# hub_exterior.net
KiCad netlist of a schematic drawn in EAGLE
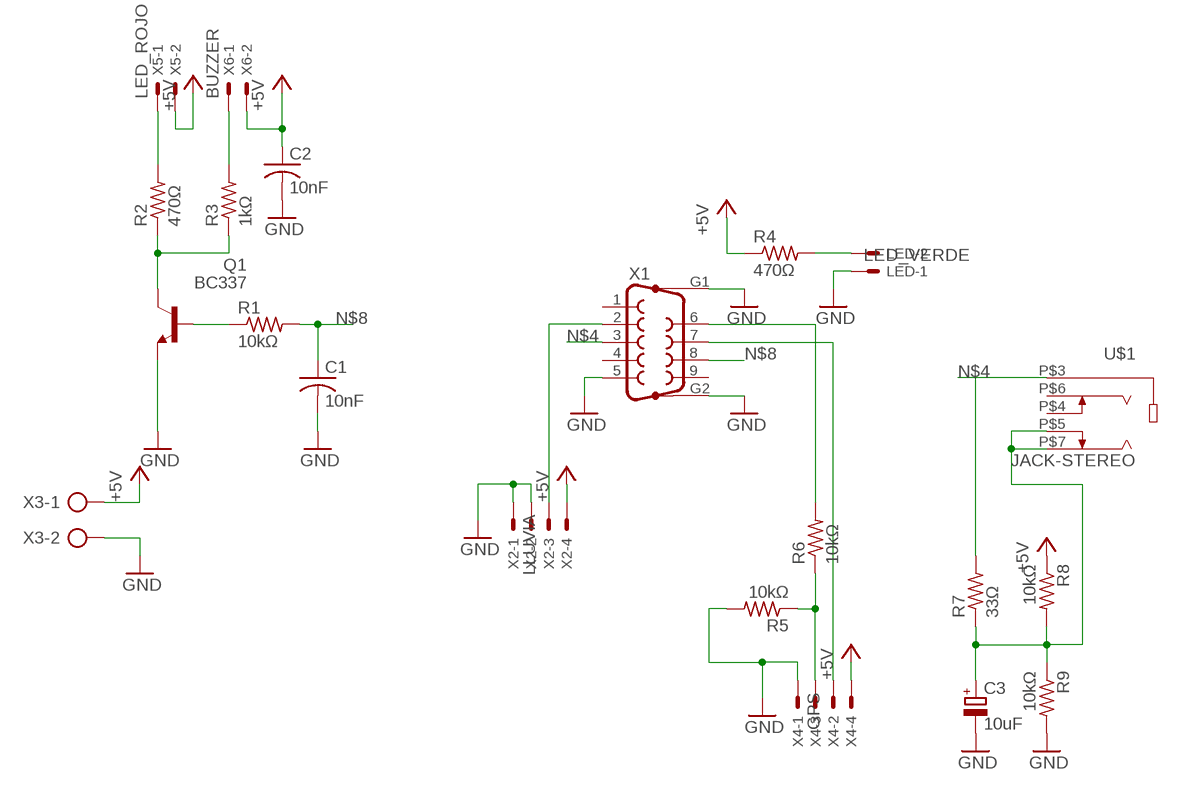
[diagram p0: schematic, sheet 1]

(export (version "E")
  (design (tool "Eeschema 10.0.6"))
  (components
    (comp (ref "C1")
      (value "10nF")
      (footprint "eagle-import:C050-025X075")
      (libsource (lib "eagle-import") (part "C-US050-025X075"))
    )
    (comp (ref "C2")
      (value "10nF")
      (footprint "eagle-import:C050-025X075")
      (libsource (lib "eagle-import") (part "C-US050-025X075"))
    )
    (comp (ref "C3")
      (value "10uF")
      (footprint "eagle-import:E2,5-5")
      (libsource (lib "eagle-import") (part "CPOL-EUE2.5-5"))
    )
    (comp (ref "LED")
      (value "LED_VERDE")
      (footprint "eagle-import:22-23-2021")
      (fields (field (name "MF") "MOLEX") (field (name "MPN") "22-23-2021"))
      (libsource (lib "eagle-import") (part "22-23-2021"))
    )
    (comp (ref "Q1")
      (value "BC337")
      (footprint "eagle-import:TO92")
      (libsource (lib "eagle-import") (part "BC337"))
    )
    (comp (ref "R1")
      (value "10kΩ")
      (footprint "eagle-import:0207_7")
      (libsource (lib "eagle-import") (part "R-US_0207/7"))
    )
    (comp (ref "R2")
      (value "470Ω")
      (footprint "eagle-import:0207_7")
      (libsource (lib "eagle-import") (part "R-US_0207/7"))
    )
    (comp (ref "R3")
      (value "1kΩ")
      (footprint "eagle-import:0207_7")
      (libsource (lib "eagle-import") (part "R-US_0207/7"))
    )
    (comp (ref "R4")
      (value "470Ω")
      (footprint "eagle-import:0207_7")
      (libsource (lib "eagle-import") (part "R-US_0207/7"))
    )
    (comp (ref "R5")
      (value "10kΩ")
      (footprint "eagle-import:0207_7")
      (libsource (lib "eagle-import") (part "R-US_0207/7"))
    )
    (comp (ref "R6")
      (value "10kΩ")
      (footprint "eagle-import:0207_15")
      (libsource (lib "eagle-import") (part "R-US_0207/15"))
    )
    (comp (ref "R7")
      (value "33Ω")
      (footprint "eagle-import:0207_7")
      (libsource (lib "eagle-import") (part "R-US_0207/7"))
    )
    (comp (ref "R8")
      (value "10kΩ")
      (footprint "eagle-import:0207_7")
      (libsource (lib "eagle-import") (part "R-US_0207/7"))
    )
    (comp (ref "R9")
      (value "10kΩ")
      (footprint "eagle-import:0207_7")
      (libsource (lib "eagle-import") (part "R-US_0207/7"))
    )
    (comp (ref "U$1")
      (value "JACK-STEREO")
      (footprint "eagle-import:SPC21348")
      (libsource (lib "eagle-import") (part "JACK-STEREO"))
    )
    (comp (ref "X1")
      (value "F09HP")
      (footprint "eagle-import:F09HP")
      (libsource (lib "eagle-import") (part "F09HP"))
    )
    (comp (ref "X2")
      (value "LLUVIA")
      (footprint "eagle-import:22-23-2041")
      (fields (field (name "MF") "MOLEX") (field (name "MPN") "22-23-2041"))
      (libsource (lib "eagle-import") (part "22-23-2041"))
    )
    (comp (ref "X3")
      (value "AK500/2")
      (footprint "eagle-import:AK500_2")
      (libsource (lib "eagle-import") (part "AK500/2"))
    )
    (comp (ref "X4")
      (value "GPS")
      (footprint "eagle-import:22-23-2041")
      (fields (field (name "MF") "MOLEX") (field (name "MPN") "22-23-2041"))
      (libsource (lib "eagle-import") (part "22-23-2041"))
    )
    (comp (ref "X5")
      (value "LED_ROJO")
      (footprint "eagle-import:22-23-2021")
      (fields (field (name "MF") "MOLEX") (field (name "MPN") "22-23-2021"))
      (libsource (lib "eagle-import") (part "22-23-2021"))
    )
    (comp (ref "X6")
      (value "BUZZER")
      (footprint "eagle-import:22-23-2021")
      (fields (field (name "MF") "MOLEX") (field (name "MPN") "22-23-2021"))
      (libsource (lib "eagle-import") (part "22-23-2021"))
    )
  )
  (nets
    (net (code "1") (name "+5V") (class "Default")
      (node (ref "C2") (pin "1") (pinfunction "1_1") (pintype "passive"))
      (node (ref "R4") (pin "1") (pinfunction "1_1") (pintype "passive"))
      (node (ref "R8") (pin "1") (pinfunction "1_1") (pintype "passive"))
      (node (ref "X2") (pin "4") (pinfunction "S_4") (pintype "passive"))
      (node (ref "X3") (pin "1") (pinfunction "KL_1") (pintype "passive"))
      (node (ref "X4") (pin "4") (pinfunction "S_4") (pintype "passive"))
      (node (ref "X5") (pin "2") (pinfunction "S_2") (pintype "passive"))
      (node (ref "X6") (pin "2") (pinfunction "S_2") (pintype "passive"))
    )
    (net (code "2") (name "/N$4") (class "Default")
      (node (ref "R7") (pin "2") (pinfunction "2_2") (pintype "passive"))
      (node (ref "U$1") (pin "P$3") (pinfunction "1_P$3") (pintype "passive"))
      (node (ref "X1") (pin "3") (pinfunction "3_3") (pintype "passive"))
    )
    (net (code "3") (name "/N$8") (class "Default")
      (node (ref "C1") (pin "1") (pinfunction "1_1") (pintype "passive"))
      (node (ref "R1") (pin "2") (pinfunction "2_2") (pintype "passive"))
      (node (ref "X1") (pin "8") (pinfunction "8_8") (pintype "passive"))
    )
    (net (code "4") (name "GND") (class "Default")
      (node (ref "C1") (pin "2") (pinfunction "2_2") (pintype "passive"))
      (node (ref "C2") (pin "2") (pinfunction "2_2") (pintype "passive"))
      (node (ref "C3") (pin "-") (pinfunction "-_-") (pintype "passive"))
      (node (ref "LED") (pin "1") (pinfunction "S_1") (pintype "passive"))
      (node (ref "Q1") (pin "1") (pinfunction "E_1") (pintype "passive"))
      (node (ref "R5") (pin "2") (pinfunction "2_2") (pintype "passive"))
      (node (ref "R9") (pin "2") (pinfunction "2_2") (pintype "passive"))
      (node (ref "X1") (pin "5") (pinfunction "5_5") (pintype "passive"))
      (node (ref "X1") (pin "G1") (pinfunction "G1_G1") (pintype "passive"))
      (node (ref "X1") (pin "G2") (pinfunction "G2_G2") (pintype "passive"))
      (node (ref "X2") (pin "1") (pinfunction "S_1") (pintype "passive"))
      (node (ref "X2") (pin "2") (pinfunction "S_2") (pintype "passive"))
      (node (ref "X3") (pin "2") (pinfunction "KL_2") (pintype "passive"))
      (node (ref "X4") (pin "1") (pinfunction "S_1") (pintype "passive"))
    )
    (net (code "5") (name "Net-(LEDB-S)") (class "Default")
      (node (ref "LED") (pin "2") (pinfunction "S_2") (pintype "passive"))
      (node (ref "R4") (pin "2") (pinfunction "2_2") (pintype "passive"))
    )
    (net (code "6") (name "Net-(Q1-B)") (class "Default")
      (node (ref "Q1") (pin "2") (pinfunction "B_2") (pintype "passive"))
      (node (ref "R1") (pin "1") (pinfunction "1_1") (pintype "passive"))
    )
    (net (code "7") (name "Net-(Q1-C)") (class "Default")
      (node (ref "Q1") (pin "3") (pinfunction "C_3") (pintype "passive"))
      (node (ref "R2") (pin "1") (pinfunction "1_1") (pintype "passive"))
      (node (ref "R3") (pin "1") (pinfunction "1_1") (pintype "passive"))
    )
    (net (code "8") (name "Net-(R6-Pad2)") (class "Default")
      (node (ref "R6") (pin "2") (pinfunction "2_2") (pintype "passive"))
      (node (ref "X1") (pin "6") (pinfunction "6_6") (pintype "passive"))
    )
    (net (code "9") (name "Net-(U$1-4)") (class "Default")
      (node (ref "C3") (pin "+") (pinfunction "+_+") (pintype "passive"))
      (node (ref "R7") (pin "1") (pinfunction "1_1") (pintype "passive"))
      (node (ref "R8") (pin "2") (pinfunction "2_2") (pintype "passive"))
      (node (ref "R9") (pin "1") (pinfunction "1_1") (pintype "passive"))
      (node (ref "U$1") (pin "P$5") (pinfunction "4_P$5") (pintype "passive"))
      (node (ref "U$1") (pin "P$7") (pinfunction "5_P$7") (pintype "passive"))
    )
    (net (code "10") (name "Net-(X2C-S)") (class "Default")
      (node (ref "X1") (pin "2") (pinfunction "2_2") (pintype "passive"))
      (node (ref "X2") (pin "3") (pinfunction "S_3") (pintype "passive"))
    )
    (net (code "11") (name "Net-(X4B-S)") (class "Default")
      (node (ref "X1") (pin "7") (pinfunction "7_7") (pintype "passive"))
      (node (ref "X4") (pin "2") (pinfunction "S_2") (pintype "passive"))
    )
    (net (code "12") (name "Net-(X4C-S)") (class "Default")
      (node (ref "R5") (pin "1") (pinfunction "1_1") (pintype "passive"))
      (node (ref "R6") (pin "1") (pinfunction "1_1") (pintype "passive"))
      (node (ref "X4") (pin "3") (pinfunction "S_3") (pintype "passive"))
    )
    (net (code "13") (name "Net-(X5A-S)") (class "Default")
      (node (ref "R2") (pin "2") (pinfunction "2_2") (pintype "passive"))
      (node (ref "X5") (pin "1") (pinfunction "S_1") (pintype "passive"))
    )
    (net (code "14") (name "Net-(X6A-S)") (class "Default")
      (node (ref "R3") (pin "2") (pinfunction "2_2") (pintype "passive"))
      (node (ref "X6") (pin "1") (pinfunction "S_1") (pintype "passive"))
    )
    (net (code "15") (name "unconnected-(U$1-2-PadP$6)") (class "Default")
      (node (ref "U$1") (pin "P$6") (pinfunction "2_P$6") (pintype "passive"))
    )
    (net (code "16") (name "unconnected-(U$1-3-PadP$4)") (class "Default")
      (node (ref "U$1") (pin "P$4") (pinfunction "3_P$4") (pintype "passive"))
    )
    (net (code "17") (name "unconnected-(X1-Pad1)") (class "Default")
      (node (ref "X1") (pin "1") (pinfunction "1_1") (pintype "passive"))
    )
    (net (code "18") (name "unconnected-(X1-Pad4)") (class "Default")
      (node (ref "X1") (pin "4") (pinfunction "4_4") (pintype "passive"))
    )
    (net (code "19") (name "unconnected-(X1-Pad9)") (class "Default")
      (node (ref "X1") (pin "9") (pinfunction "9_9") (pintype "passive"))
    )
  )
)
